# FPGA_B34.net
KiCad netlist of a schematic drawn in Altium Designer
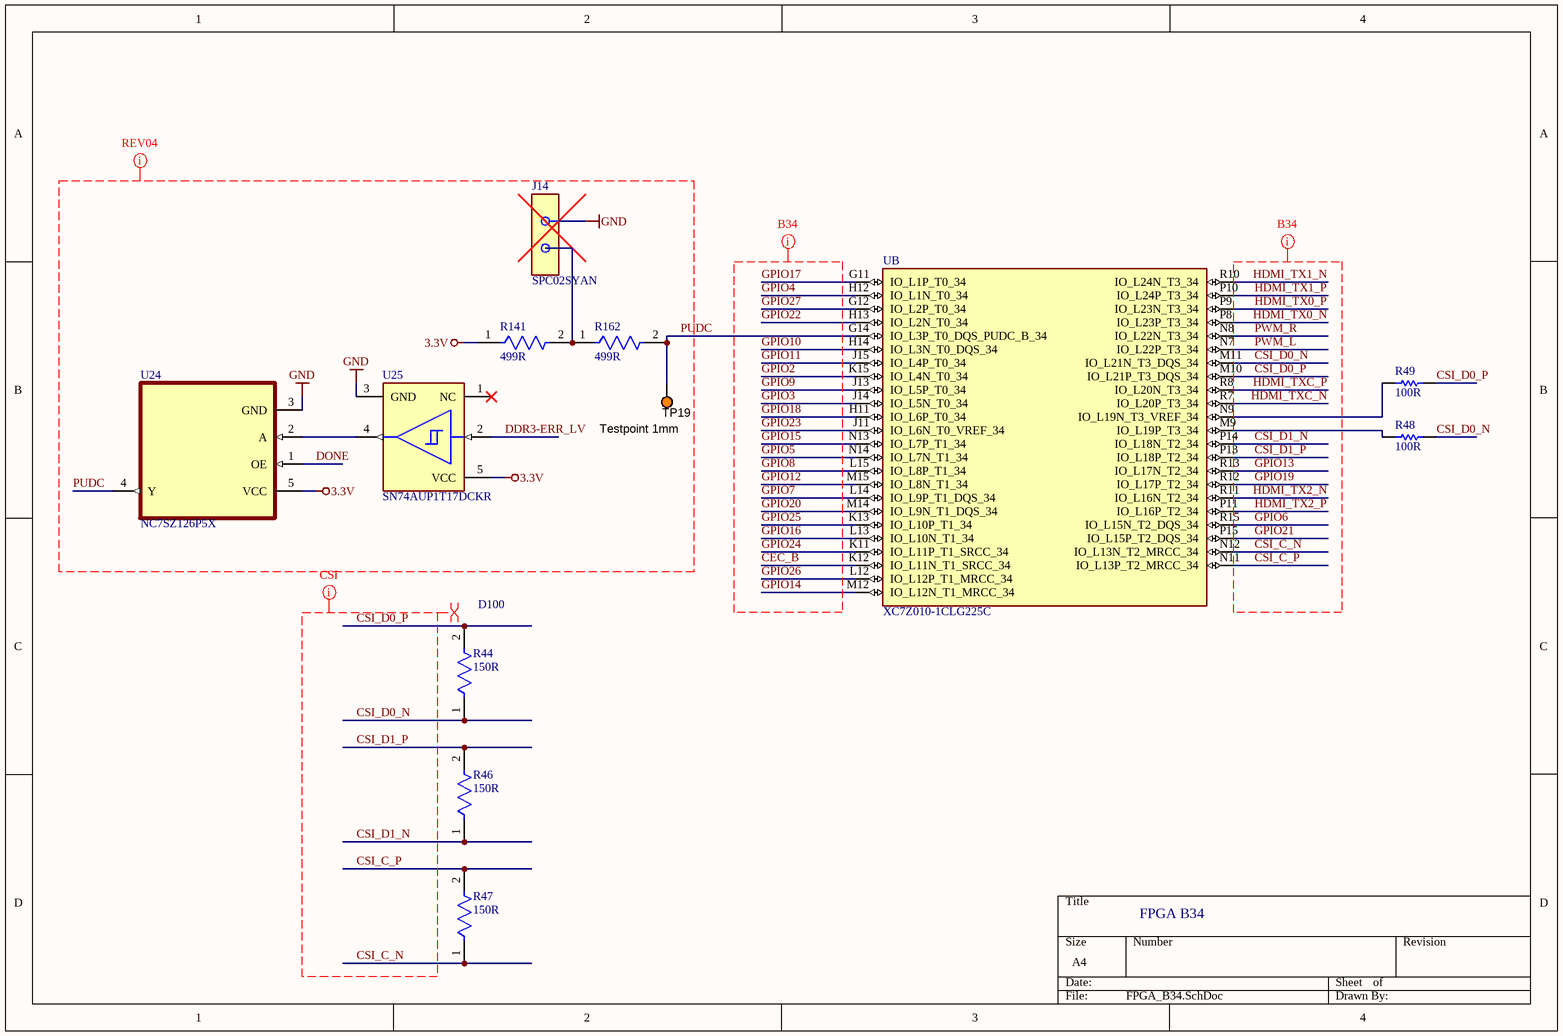
[diagram p0: FPGA_B34.SchDoc]

(export (version "E")
  (design (tool "Eeschema 10.0.6"))
  (components
    (comp (ref "J14")
      (value "SPC02SYAN")
      (footprint "FP-SPC02SYAN-MFG")
      (description "CONN JUMPER SHORTING GOLD FLASH")
      (libsource (lib "Altium Content Vault") (part "728c6cbc3517dff9de184b23a534e16"))
    )
    (comp (ref "R44")
      (value "150R")
      (footprint "FP-RT0402-MFG")
      (description "RES SMD 150 OHM 0.1% 1/16W 0402")
      (fields
        (field (name "MANUFACTURER") "Yageo")
        (field (name "MANUFACTURER PART NUMBER") "RT0402BRD07150RL")
      )
      (libsource (lib "Altium Content Vault") (part "1029c3af85768c4190bb7ad29bc67b5"))
    )
    (comp (ref "R46")
      (value "150R")
      (footprint "FP-RT0402-MFG")
      (description "RES SMD 150 OHM 0.1% 1/16W 0402")
      (fields
        (field (name "MANUFACTURER") "Yageo")
        (field (name "MANUFACTURER PART NUMBER") "RT0402BRD07150RL")
      )
      (libsource (lib "Altium Content Vault") (part "1029c3af85768c4190bb7ad29bc67b5"))
    )
    (comp (ref "R47")
      (value "150R")
      (footprint "FP-RT0402-MFG")
      (description "RES SMD 150 OHM 0.1% 1/16W 0402")
      (fields
        (field (name "MANUFACTURER") "Yageo")
        (field (name "MANUFACTURER PART NUMBER") "RT0402BRD07150RL")
      )
      (libsource (lib "Altium Content Vault") (part "1029c3af85768c4190bb7ad29bc67b5"))
    )
    (comp (ref "R48")
      (value "100R")
      (footprint "RESC0603X28X15LL05T05")
      (fields (field (name "PART NUMBER") "CRCW0201100RJNED") (field (name "MANUFACTURER") "Vishay"))
      (libsource (lib "Altium Content Vault") (part "RES"))
    )
    (comp (ref "R49")
      (value "100R")
      (footprint "RESC0603X28X15LL05T05")
      (fields (field (name "PART NUMBER") "CRCW0201100RJNED") (field (name "MANUFACTURER") "Vishay"))
      (libsource (lib "Altium Content Vault") (part "RES"))
    )
    (comp (ref "R141")
      (value "499R")
      (footprint "FP-RQ731J-IPC_C")
      (description "RQ73 0603 499Ω  0.15W 10ppm/°C 0.1% 75V")
      (fields (field (name "MANUFACTURER") "TE") (field (name "TOLERANCE") "0.1%"))
      (libsource (lib "Altium Content Vault") (part "1029c3af85768c4190bb7ad29bc67b5"))
    )
    (comp (ref "R162")
      (value "499R")
      (footprint "FP-RQ731J-IPC_C")
      (description "RQ73 0603 499Ω  0.15W 10ppm/°C 0.1% 75V")
      (fields (field (name "MANUFACTURER") "TE") (field (name "TOLERANCE") "0.1%"))
      (libsource (lib "Altium Content Vault") (part "1029c3af85768c4190bb7ad29bc67b5"))
    )
    (comp (ref "TP19")
      (value "Testpoint 1mm")
      (footprint "KSTN-5003")
      (description "Test Point, Orange, 1-Pin THD, RoHS")
      (libsource (lib "Altium Content Vault") (part "TESTPOINT_ORANGE"))
    )
    (comp (ref "U")
      (value "XC7Z010-1CLG225C")
      (footprint "BGA225C80P15X15_1300X1300X150")
      (fields (field (name "MF") "Xilinx Inc.") (field (name "DIGI-KEY_PART_NUMBER") "122-1855-ND"))
      (libsource (lib "XC7Z010-1CLG225C (2)") (part "XC7Z010-1CLG225C"))
    )
    (comp (ref "U24")
      (value "NC7SZ126P5X")
      (footprint "SOT65P210X110-5N")
      (description "Buffer, Non-Inverting 1 Element 1 Bit per Element 3-State Output SC-70-5")
      (fields (field (name "MF") "ON Semiconductor"))
      (libsource (lib "NC7SZ126P5X") (part "NC7SZ126P5X"))
    )
    (comp (ref "U25")
      (value "SN74AUP1T17DCKR")
      (footprint "FP-DCK0005A-IPC_B")
      (description "IC BUF NON-INVERT 3.6V SC70-5")
      (libsource (lib "Altium Content Vault") (part "13663c114c60c392ae5ab8dc83cb180"))
    )
  )
  (nets
    (net (code "1") (name "/CEC_B") (class "Default")
      (node (ref "U") (pin "K12") (pinfunction "IO_L11N_T1_SRCC_34_K12") (pintype "bidirectional"))
    )
    (net (code "2") (name "/CSI_C_N") (class "Default")
      (node (ref "R47") (pin "1") (pinfunction "1_1") (pintype "passive"))
      (node (ref "U") (pin "N12") (pinfunction "IO_L13N_T2_MRCC_34_N12") (pintype "bidirectional"))
    )
    (net (code "3") (name "/CSI_C_P") (class "Default")
      (node (ref "R47") (pin "2") (pinfunction "2_2") (pintype "passive"))
      (node (ref "U") (pin "N11") (pinfunction "IO_L13P_T2_MRCC_34_N11") (pintype "bidirectional"))
    )
    (net (code "4") (name "/CSI_D0_N") (class "Default")
      (node (ref "R44") (pin "1") (pinfunction "1_1") (pintype "passive"))
      (node (ref "R48") (pin "2") (pinfunction "2_2") (pintype "passive"))
      (node (ref "U") (pin "M11") (pinfunction "IO_L21N_T3_DQS_34_M11") (pintype "bidirectional"))
    )
    (net (code "5") (name "/CSI_D0_P") (class "Default")
      (node (ref "R44") (pin "2") (pinfunction "2_2") (pintype "passive"))
      (node (ref "R49") (pin "2") (pinfunction "2_2") (pintype "passive"))
      (node (ref "U") (pin "M10") (pinfunction "IO_L21P_T3_DQS_34_M10") (pintype "bidirectional"))
    )
    (net (code "6") (name "/CSI_D1_N") (class "Default")
      (node (ref "R46") (pin "1") (pinfunction "1_1") (pintype "passive"))
      (node (ref "U") (pin "P14") (pinfunction "IO_L18N_T2_34_P14") (pintype "bidirectional"))
    )
    (net (code "7") (name "/CSI_D1_P") (class "Default")
      (node (ref "R46") (pin "2") (pinfunction "2_2") (pintype "passive"))
      (node (ref "U") (pin "P13") (pinfunction "IO_L18P_T2_34_P13") (pintype "bidirectional"))
    )
    (net (code "8") (name "/DDR3-ERR_LV") (class "Default")
      (node (ref "U25") (pin "2") (pinfunction "A_2") (pintype "input"))
    )
    (net (code "9") (name "/DONE") (class "Default")
      (node (ref "U24") (pin "1") (pinfunction "OE_1") (pintype "input"))
    )
    (net (code "10") (name "/GPIO2") (class "Default")
      (node (ref "U") (pin "K15") (pinfunction "IO_L4N_T0_34_K15") (pintype "bidirectional"))
    )
    (net (code "11") (name "/GPIO3") (class "Default")
      (node (ref "U") (pin "J14") (pinfunction "IO_L5N_T0_34_J14") (pintype "bidirectional"))
    )
    (net (code "12") (name "/GPIO4") (class "Default")
      (node (ref "U") (pin "H12") (pinfunction "IO_L1N_T0_34_H12") (pintype "bidirectional"))
    )
    (net (code "13") (name "/GPIO5") (class "Default")
      (node (ref "U") (pin "N14") (pinfunction "IO_L7N_T1_34_N14") (pintype "bidirectional"))
    )
    (net (code "14") (name "/GPIO6") (class "Default")
      (node (ref "U") (pin "R15") (pinfunction "IO_L15N_T2_DQS_34_R15") (pintype "bidirectional"))
    )
    (net (code "15") (name "/GPIO7") (class "Default")
      (node (ref "U") (pin "L14") (pinfunction "IO_L9P_T1_DQS_34_L14") (pintype "bidirectional"))
    )
    (net (code "16") (name "/GPIO8") (class "Default")
      (node (ref "U") (pin "L15") (pinfunction "IO_L8P_T1_34_L15") (pintype "bidirectional"))
    )
    (net (code "17") (name "/GPIO9") (class "Default")
      (node (ref "U") (pin "J13") (pinfunction "IO_L5P_T0_34_J13") (pintype "bidirectional"))
    )
    (net (code "18") (name "/GPIO10") (class "Default")
      (node (ref "U") (pin "H14") (pinfunction "IO_L3N_T0_DQS_34_H14") (pintype "bidirectional"))
    )
    (net (code "19") (name "/GPIO11") (class "Default")
      (node (ref "U") (pin "J15") (pinfunction "IO_L4P_T0_34_J15") (pintype "bidirectional"))
    )
    (net (code "20") (name "/GPIO12") (class "Default")
      (node (ref "U") (pin "M15") (pinfunction "IO_L8N_T1_34_M15") (pintype "bidirectional"))
    )
    (net (code "21") (name "/GPIO13") (class "Default")
      (node (ref "U") (pin "R13") (pinfunction "IO_L17N_T2_34_R13") (pintype "bidirectional"))
    )
    (net (code "22") (name "/GPIO14") (class "Default")
      (node (ref "U") (pin "M12") (pinfunction "IO_L12N_T1_MRCC_34_M12") (pintype "bidirectional"))
    )
    (net (code "23") (name "/GPIO15") (class "Default")
      (node (ref "U") (pin "N13") (pinfunction "IO_L7P_T1_34_N13") (pintype "bidirectional"))
    )
    (net (code "24") (name "/GPIO16") (class "Default")
      (node (ref "U") (pin "L13") (pinfunction "IO_L10N_T1_34_L13") (pintype "bidirectional"))
    )
    (net (code "25") (name "/GPIO17") (class "Default")
      (node (ref "U") (pin "G11") (pinfunction "IO_L1P_T0_34_G11") (pintype "bidirectional"))
    )
    (net (code "26") (name "/GPIO18") (class "Default")
      (node (ref "U") (pin "H11") (pinfunction "IO_L6P_T0_34_H11") (pintype "bidirectional"))
    )
    (net (code "27") (name "/GPIO19") (class "Default")
      (node (ref "U") (pin "R12") (pinfunction "IO_L17P_T2_34_R12") (pintype "bidirectional"))
    )
    (net (code "28") (name "/GPIO20") (class "Default")
      (node (ref "U") (pin "M14") (pinfunction "IO_L9N_T1_DQS_34_M14") (pintype "bidirectional"))
    )
    (net (code "29") (name "/GPIO21") (class "Default")
      (node (ref "U") (pin "P15") (pinfunction "IO_L15P_T2_DQS_34_P15") (pintype "bidirectional"))
    )
    (net (code "30") (name "/GPIO22") (class "Default")
      (node (ref "U") (pin "H13") (pinfunction "IO_L2N_T0_34_H13") (pintype "bidirectional"))
    )
    (net (code "31") (name "/GPIO23") (class "Default")
      (node (ref "U") (pin "J11") (pinfunction "IO_L6N_T0_VREF_34_J11") (pintype "bidirectional"))
    )
    (net (code "32") (name "/GPIO24") (class "Default")
      (node (ref "U") (pin "K11") (pinfunction "IO_L11P_T1_SRCC_34_K11") (pintype "bidirectional"))
    )
    (net (code "33") (name "/GPIO25") (class "Default")
      (node (ref "U") (pin "K13") (pinfunction "IO_L10P_T1_34_K13") (pintype "bidirectional"))
    )
    (net (code "34") (name "/GPIO26") (class "Default")
      (node (ref "U") (pin "L12") (pinfunction "IO_L12P_T1_MRCC_34_L12") (pintype "bidirectional"))
    )
    (net (code "35") (name "/GPIO27") (class "Default")
      (node (ref "U") (pin "G12") (pinfunction "IO_L2P_T0_34_G12") (pintype "bidirectional"))
    )
    (net (code "36") (name "/HDMI_TX0_N") (class "Default")
      (node (ref "U") (pin "P8") (pinfunction "IO_L23P_T3_34_P8") (pintype "bidirectional"))
    )
    (net (code "37") (name "/HDMI_TX0_P") (class "Default")
      (node (ref "U") (pin "P9") (pinfunction "IO_L23N_T3_34_P9") (pintype "bidirectional"))
    )
    (net (code "38") (name "/HDMI_TX1_N") (class "Default")
      (node (ref "U") (pin "R10") (pinfunction "IO_L24N_T3_34_R10") (pintype "bidirectional"))
    )
    (net (code "39") (name "/HDMI_TX1_P") (class "Default")
      (node (ref "U") (pin "P10") (pinfunction "IO_L24P_T3_34_P10") (pintype "bidirectional"))
    )
    (net (code "40") (name "/HDMI_TX2_N") (class "Default")
      (node (ref "U") (pin "R11") (pinfunction "IO_L16N_T2_34_R11") (pintype "bidirectional"))
    )
    (net (code "41") (name "/HDMI_TX2_P") (class "Default")
      (node (ref "U") (pin "P11") (pinfunction "IO_L16P_T2_34_P11") (pintype "bidirectional"))
    )
    (net (code "42") (name "/HDMI_TXC_N") (class "Default")
      (node (ref "U") (pin "R7") (pinfunction "IO_L20P_T3_34_R7") (pintype "bidirectional"))
    )
    (net (code "43") (name "/HDMI_TXC_P") (class "Default")
      (node (ref "U") (pin "R8") (pinfunction "IO_L20N_T3_34_R8") (pintype "bidirectional"))
    )
    (net (code "44") (name "/PUDC") (class "Default")
      (node (ref "R162") (pin "2") (pinfunction "2_2") (pintype "passive"))
      (node (ref "TP19") (pin "1") (pinfunction "1_1") (pintype "passive"))
      (node (ref "U") (pin "G14") (pinfunction "IO_L3P_T0_DQS_PUDC_B_34_G14") (pintype "bidirectional"))
      (node (ref "U24") (pin "4") (pinfunction "Y_4") (pintype "output"))
    )
    (net (code "45") (name "/PWM_L") (class "Default")
      (node (ref "U") (pin "N7") (pinfunction "IO_L22P_T3_34_N7") (pintype "bidirectional"))
    )
    (net (code "46") (name "/PWM_R") (class "Default")
      (node (ref "U") (pin "N8") (pinfunction "IO_L22N_T3_34_N8") (pintype "bidirectional"))
    )
    (net (code "47") (name "3.3V") (class "Default")
      (node (ref "R141") (pin "1") (pinfunction "1_1") (pintype "passive"))
      (node (ref "U24") (pin "5") (pinfunction "VCC_5") (pintype "power_in"))
      (node (ref "U25") (pin "5") (pinfunction "VCC_5") (pintype "power_in"))
    )
    (net (code "48") (name "GND") (class "Default")
      (node (ref "U24") (pin "3") (pinfunction "GND_3") (pintype "passive"))
      (node (ref "U25") (pin "3") (pinfunction "GND_3") (pintype "power_in"))
    )
    (net (code "49") (name "Net-(R141-Pad2)") (class "Default")
      (node (ref "R141") (pin "2") (pinfunction "2_2") (pintype "passive"))
      (node (ref "R162") (pin "1") (pinfunction "1_1") (pintype "passive"))
    )
    (net (code "50") (name "Net-(U24-A)") (class "Default")
      (node (ref "U24") (pin "2") (pinfunction "A_2") (pintype "input"))
      (node (ref "U25") (pin "4") (pinfunction "Y_4") (pintype "output"))
    )
    (net (code "51") (name "Net-(UB-IO_L19N_T3_VREF_34)") (class "Default")
      (node (ref "R49") (pin "1") (pinfunction "1_1") (pintype "passive"))
      (node (ref "U") (pin "N9") (pinfunction "IO_L19N_T3_VREF_34_N9") (pintype "bidirectional"))
    )
    (net (code "52") (name "Net-(UB-IO_L19P_T3_34)") (class "Default")
      (node (ref "R48") (pin "1") (pinfunction "1_1") (pintype "passive"))
      (node (ref "U") (pin "M9") (pinfunction "IO_L19P_T3_34_M9") (pintype "bidirectional"))
    )
    (net (code "53") (name "unconnected-(U25-NC-Pad1)") (class "Default")
      (node (ref "U25") (pin "1") (pinfunction "NC_1") (pintype "passive+no_connect"))
    )
  )
)
